# MAX31856_BREAKOUT_x4.net
KiCad netlist of a schematic drawn in EAGLE
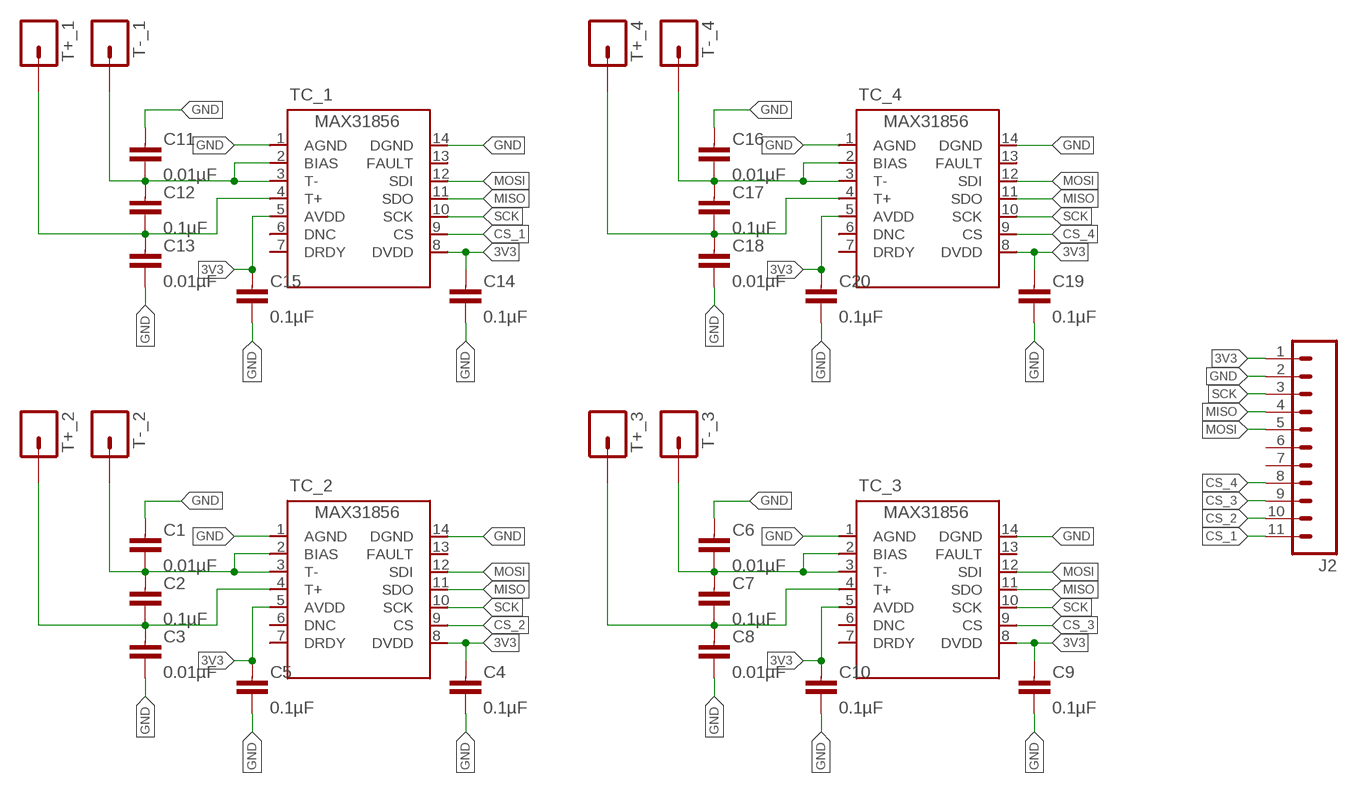
[diagram p0: schematic, sheet 1]

(export (version "E")
  (design (tool "Eeschema 10.0.6"))
  (components
    (comp (ref "C1")
      (value "0.01µF")
      (footprint "eagle-import:C0603-N")
      (libsource (lib "eagle-import") (part "CAPACITOR0603-N"))
    )
    (comp (ref "C2")
      (value "0.1µF")
      (footprint "eagle-import:C0603-N")
      (libsource (lib "eagle-import") (part "CAPACITOR0603-N"))
    )
    (comp (ref "C3")
      (value "0.01µF")
      (footprint "eagle-import:C0603-N")
      (libsource (lib "eagle-import") (part "CAPACITOR0603-N"))
    )
    (comp (ref "C4")
      (value "0.1µF")
      (footprint "eagle-import:C0603-N")
      (libsource (lib "eagle-import") (part "CAPACITOR0603-N"))
    )
    (comp (ref "C5")
      (value "0.1µF")
      (footprint "eagle-import:C0603-N")
      (libsource (lib "eagle-import") (part "CAPACITOR0603-N"))
    )
    (comp (ref "C6")
      (value "0.01µF")
      (footprint "eagle-import:C0603-N")
      (libsource (lib "eagle-import") (part "CAPACITOR0603-N"))
    )
    (comp (ref "C7")
      (value "0.1µF")
      (footprint "eagle-import:C0603-N")
      (libsource (lib "eagle-import") (part "CAPACITOR0603-N"))
    )
    (comp (ref "C8")
      (value "0.01µF")
      (footprint "eagle-import:C0603-N")
      (libsource (lib "eagle-import") (part "CAPACITOR0603-N"))
    )
    (comp (ref "C9")
      (value "0.1µF")
      (footprint "eagle-import:C0603-N")
      (libsource (lib "eagle-import") (part "CAPACITOR0603-N"))
    )
    (comp (ref "C10")
      (value "0.1µF")
      (footprint "eagle-import:C0603-N")
      (libsource (lib "eagle-import") (part "CAPACITOR0603-N"))
    )
    (comp (ref "C11")
      (value "0.01µF")
      (footprint "eagle-import:C0603-N")
      (libsource (lib "eagle-import") (part "CAPACITOR0603-N"))
    )
    (comp (ref "C12")
      (value "0.1µF")
      (footprint "eagle-import:C0603-N")
      (libsource (lib "eagle-import") (part "CAPACITOR0603-N"))
    )
    (comp (ref "C13")
      (value "0.01µF")
      (footprint "eagle-import:C0603-N")
      (libsource (lib "eagle-import") (part "CAPACITOR0603-N"))
    )
    (comp (ref "C14")
      (value "0.1µF")
      (footprint "eagle-import:C0603-N")
      (libsource (lib "eagle-import") (part "CAPACITOR0603-N"))
    )
    (comp (ref "C15")
      (value "0.1µF")
      (footprint "eagle-import:C0603-N")
      (libsource (lib "eagle-import") (part "CAPACITOR0603-N"))
    )
    (comp (ref "C16")
      (value "0.01µF")
      (footprint "eagle-import:C0603-N")
      (libsource (lib "eagle-import") (part "CAPACITOR0603-N"))
    )
    (comp (ref "C17")
      (value "0.1µF")
      (footprint "eagle-import:C0603-N")
      (libsource (lib "eagle-import") (part "CAPACITOR0603-N"))
    )
    (comp (ref "C18")
      (value "0.01µF")
      (footprint "eagle-import:C0603-N")
      (libsource (lib "eagle-import") (part "CAPACITOR0603-N"))
    )
    (comp (ref "C19")
      (value "0.1µF")
      (footprint "eagle-import:C0603-N")
      (libsource (lib "eagle-import") (part "CAPACITOR0603-N"))
    )
    (comp (ref "C20")
      (value "0.1µF")
      (footprint "eagle-import:C0603-N")
      (libsource (lib "eagle-import") (part "CAPACITOR0603-N"))
    )
    (comp (ref "J2")
      (value "M11PTH")
      (footprint "eagle-import:1X11")
      (libsource (lib "eagle-import") (part "M11PTH"))
    )
    (comp (ref "T+_1")
      (value "M01SMD")
      (footprint "eagle-import:LUXEON-PAD")
      (libsource (lib "eagle-import") (part "M01SMD"))
    )
    (comp (ref "T+_2")
      (value "M01SMD")
      (footprint "eagle-import:LUXEON-PAD")
      (libsource (lib "eagle-import") (part "M01SMD"))
    )
    (comp (ref "T+_3")
      (value "M01SMD")
      (footprint "eagle-import:LUXEON-PAD")
      (libsource (lib "eagle-import") (part "M01SMD"))
    )
    (comp (ref "T+_4")
      (value "M01SMD")
      (footprint "eagle-import:LUXEON-PAD")
      (libsource (lib "eagle-import") (part "M01SMD"))
    )
    (comp (ref "T-_1")
      (value "M01SMD")
      (footprint "eagle-import:LUXEON-PAD")
      (libsource (lib "eagle-import") (part "M01SMD"))
    )
    (comp (ref "T-_2")
      (value "M01SMD")
      (footprint "eagle-import:LUXEON-PAD")
      (libsource (lib "eagle-import") (part "M01SMD"))
    )
    (comp (ref "T-_3")
      (value "M01SMD")
      (footprint "eagle-import:LUXEON-PAD")
      (libsource (lib "eagle-import") (part "M01SMD"))
    )
    (comp (ref "T-_4")
      (value "M01SMD")
      (footprint "eagle-import:LUXEON-PAD")
      (libsource (lib "eagle-import") (part "M01SMD"))
    )
    (comp (ref "TC_1")
      (value "MAX31856MUD+")
      (footprint "eagle-import:TSSOP14")
      (libsource (lib "eagle-import") (part "MAX31856MUD+"))
    )
    (comp (ref "TC_2")
      (value "MAX31856MUD+")
      (footprint "eagle-import:TSSOP14")
      (libsource (lib "eagle-import") (part "MAX31856MUD+"))
    )
    (comp (ref "TC_3")
      (value "MAX31856MUD+")
      (footprint "eagle-import:TSSOP14")
      (libsource (lib "eagle-import") (part "MAX31856MUD+"))
    )
    (comp (ref "TC_4")
      (value "MAX31856MUD+")
      (footprint "eagle-import:TSSOP14")
      (libsource (lib "eagle-import") (part "MAX31856MUD+"))
    )
  )
  (nets
    (net (code "1") (name "3V3") (class "Default")
      (node (ref "C10") (pin "1") (pinfunction "1_1") (pintype "passive"))
      (node (ref "C14") (pin "1") (pinfunction "1_1") (pintype "passive"))
      (node (ref "C15") (pin "1") (pinfunction "1_1") (pintype "passive"))
      (node (ref "C19") (pin "1") (pinfunction "1_1") (pintype "passive"))
      (node (ref "C20") (pin "1") (pinfunction "1_1") (pintype "passive"))
      (node (ref "C4") (pin "1") (pinfunction "1_1") (pintype "passive"))
      (node (ref "C5") (pin "1") (pinfunction "1_1") (pintype "passive"))
      (node (ref "C9") (pin "1") (pinfunction "1_1") (pintype "passive"))
      (node (ref "J2") (pin "1") (pinfunction "1_1") (pintype "passive"))
      (node (ref "TC_1") (pin "5") (pinfunction "AVDD_5") (pintype "bidirectional"))
      (node (ref "TC_1") (pin "8") (pinfunction "DVDD_8") (pintype "bidirectional"))
      (node (ref "TC_2") (pin "5") (pinfunction "AVDD_5") (pintype "bidirectional"))
      (node (ref "TC_2") (pin "8") (pinfunction "DVDD_8") (pintype "bidirectional"))
      (node (ref "TC_3") (pin "5") (pinfunction "AVDD_5") (pintype "bidirectional"))
      (node (ref "TC_3") (pin "8") (pinfunction "DVDD_8") (pintype "bidirectional"))
      (node (ref "TC_4") (pin "5") (pinfunction "AVDD_5") (pintype "bidirectional"))
      (node (ref "TC_4") (pin "8") (pinfunction "DVDD_8") (pintype "bidirectional"))
    )
    (net (code "2") (name "CS_1") (class "Default")
      (node (ref "J2") (pin "11") (pinfunction "11_11") (pintype "passive"))
      (node (ref "TC_1") (pin "9") (pinfunction "CS_9") (pintype "bidirectional"))
    )
    (net (code "3") (name "CS_2") (class "Default")
      (node (ref "J2") (pin "10") (pinfunction "10_10") (pintype "passive"))
      (node (ref "TC_2") (pin "9") (pinfunction "CS_9") (pintype "bidirectional"))
    )
    (net (code "4") (name "CS_3") (class "Default")
      (node (ref "J2") (pin "9") (pinfunction "9_9") (pintype "passive"))
      (node (ref "TC_3") (pin "9") (pinfunction "CS_9") (pintype "bidirectional"))
    )
    (net (code "5") (name "CS_4") (class "Default")
      (node (ref "J2") (pin "8") (pinfunction "8_8") (pintype "passive"))
      (node (ref "TC_4") (pin "9") (pinfunction "CS_9") (pintype "bidirectional"))
    )
    (net (code "6") (name "GND") (class "Default")
      (node (ref "C1") (pin "1") (pinfunction "1_1") (pintype "passive"))
      (node (ref "C10") (pin "2") (pinfunction "2_2") (pintype "passive"))
      (node (ref "C11") (pin "1") (pinfunction "1_1") (pintype "passive"))
      (node (ref "C13") (pin "2") (pinfunction "2_2") (pintype "passive"))
      (node (ref "C14") (pin "2") (pinfunction "2_2") (pintype "passive"))
      (node (ref "C15") (pin "2") (pinfunction "2_2") (pintype "passive"))
      (node (ref "C16") (pin "1") (pinfunction "1_1") (pintype "passive"))
      (node (ref "C18") (pin "2") (pinfunction "2_2") (pintype "passive"))
      (node (ref "C19") (pin "2") (pinfunction "2_2") (pintype "passive"))
      (node (ref "C20") (pin "2") (pinfunction "2_2") (pintype "passive"))
      (node (ref "C3") (pin "2") (pinfunction "2_2") (pintype "passive"))
      (node (ref "C4") (pin "2") (pinfunction "2_2") (pintype "passive"))
      (node (ref "C5") (pin "2") (pinfunction "2_2") (pintype "passive"))
      (node (ref "C6") (pin "1") (pinfunction "1_1") (pintype "passive"))
      (node (ref "C8") (pin "2") (pinfunction "2_2") (pintype "passive"))
      (node (ref "C9") (pin "2") (pinfunction "2_2") (pintype "passive"))
      (node (ref "J2") (pin "2") (pinfunction "2_2") (pintype "passive"))
      (node (ref "TC_1") (pin "1") (pinfunction "AGND_1") (pintype "bidirectional"))
      (node (ref "TC_1") (pin "14") (pinfunction "DGND_14") (pintype "bidirectional"))
      (node (ref "TC_2") (pin "1") (pinfunction "AGND_1") (pintype "bidirectional"))
      (node (ref "TC_2") (pin "14") (pinfunction "DGND_14") (pintype "bidirectional"))
      (node (ref "TC_3") (pin "1") (pinfunction "AGND_1") (pintype "bidirectional"))
      (node (ref "TC_3") (pin "14") (pinfunction "DGND_14") (pintype "bidirectional"))
      (node (ref "TC_4") (pin "1") (pinfunction "AGND_1") (pintype "bidirectional"))
      (node (ref "TC_4") (pin "14") (pinfunction "DGND_14") (pintype "bidirectional"))
    )
    (net (code "7") (name "MISO") (class "Default")
      (node (ref "J2") (pin "4") (pinfunction "4_4") (pintype "passive"))
      (node (ref "TC_1") (pin "11") (pinfunction "SDO_11") (pintype "bidirectional"))
      (node (ref "TC_2") (pin "11") (pinfunction "SDO_11") (pintype "bidirectional"))
      (node (ref "TC_3") (pin "11") (pinfunction "SDO_11") (pintype "bidirectional"))
      (node (ref "TC_4") (pin "11") (pinfunction "SDO_11") (pintype "bidirectional"))
    )
    (net (code "8") (name "MOSI") (class "Default")
      (node (ref "J2") (pin "5") (pinfunction "5_5") (pintype "passive"))
      (node (ref "TC_1") (pin "12") (pinfunction "SDI_12") (pintype "bidirectional"))
      (node (ref "TC_2") (pin "12") (pinfunction "SDI_12") (pintype "bidirectional"))
      (node (ref "TC_3") (pin "12") (pinfunction "SDI_12") (pintype "bidirectional"))
      (node (ref "TC_4") (pin "12") (pinfunction "SDI_12") (pintype "bidirectional"))
    )
    (net (code "9") (name "Net-(T+_1-1)") (class "Default")
      (node (ref "C12") (pin "2") (pinfunction "2_2") (pintype "passive"))
      (node (ref "C13") (pin "1") (pinfunction "1_1") (pintype "passive"))
      (node (ref "T+_1") (pin "P$1") (pinfunction "1_P$1") (pintype "passive"))
      (node (ref "TC_1") (pin "4") (pinfunction "T+_4") (pintype "bidirectional"))
    )
    (net (code "10") (name "Net-(T+_2-1)") (class "Default")
      (node (ref "C2") (pin "2") (pinfunction "2_2") (pintype "passive"))
      (node (ref "C3") (pin "1") (pinfunction "1_1") (pintype "passive"))
      (node (ref "T+_2") (pin "P$1") (pinfunction "1_P$1") (pintype "passive"))
      (node (ref "TC_2") (pin "4") (pinfunction "T+_4") (pintype "bidirectional"))
    )
    (net (code "11") (name "Net-(T+_3-1)") (class "Default")
      (node (ref "C7") (pin "2") (pinfunction "2_2") (pintype "passive"))
      (node (ref "C8") (pin "1") (pinfunction "1_1") (pintype "passive"))
      (node (ref "T+_3") (pin "P$1") (pinfunction "1_P$1") (pintype "passive"))
      (node (ref "TC_3") (pin "4") (pinfunction "T+_4") (pintype "bidirectional"))
    )
    (net (code "12") (name "Net-(T+_4-1)") (class "Default")
      (node (ref "C17") (pin "2") (pinfunction "2_2") (pintype "passive"))
      (node (ref "C18") (pin "1") (pinfunction "1_1") (pintype "passive"))
      (node (ref "T+_4") (pin "P$1") (pinfunction "1_P$1") (pintype "passive"))
      (node (ref "TC_4") (pin "4") (pinfunction "T+_4") (pintype "bidirectional"))
    )
    (net (code "13") (name "Net-(T-_1-1)") (class "Default")
      (node (ref "C11") (pin "2") (pinfunction "2_2") (pintype "passive"))
      (node (ref "C12") (pin "1") (pinfunction "1_1") (pintype "passive"))
      (node (ref "T-_1") (pin "P$1") (pinfunction "1_P$1") (pintype "passive"))
      (node (ref "TC_1") (pin "2") (pinfunction "BIAS_2") (pintype "bidirectional"))
      (node (ref "TC_1") (pin "3") (pinfunction "T-_3") (pintype "bidirectional"))
    )
    (net (code "14") (name "Net-(T-_2-1)") (class "Default")
      (node (ref "C1") (pin "2") (pinfunction "2_2") (pintype "passive"))
      (node (ref "C2") (pin "1") (pinfunction "1_1") (pintype "passive"))
      (node (ref "T-_2") (pin "P$1") (pinfunction "1_P$1") (pintype "passive"))
      (node (ref "TC_2") (pin "2") (pinfunction "BIAS_2") (pintype "bidirectional"))
      (node (ref "TC_2") (pin "3") (pinfunction "T-_3") (pintype "bidirectional"))
    )
    (net (code "15") (name "Net-(T-_3-1)") (class "Default")
      (node (ref "C6") (pin "2") (pinfunction "2_2") (pintype "passive"))
      (node (ref "C7") (pin "1") (pinfunction "1_1") (pintype "passive"))
      (node (ref "T-_3") (pin "P$1") (pinfunction "1_P$1") (pintype "passive"))
      (node (ref "TC_3") (pin "2") (pinfunction "BIAS_2") (pintype "bidirectional"))
      (node (ref "TC_3") (pin "3") (pinfunction "T-_3") (pintype "bidirectional"))
    )
    (net (code "16") (name "Net-(T-_4-1)") (class "Default")
      (node (ref "C16") (pin "2") (pinfunction "2_2") (pintype "passive"))
      (node (ref "C17") (pin "1") (pinfunction "1_1") (pintype "passive"))
      (node (ref "T-_4") (pin "P$1") (pinfunction "1_P$1") (pintype "passive"))
      (node (ref "TC_4") (pin "2") (pinfunction "BIAS_2") (pintype "bidirectional"))
      (node (ref "TC_4") (pin "3") (pinfunction "T-_3") (pintype "bidirectional"))
    )
    (net (code "17") (name "SCK") (class "Default")
      (node (ref "J2") (pin "3") (pinfunction "3_3") (pintype "passive"))
      (node (ref "TC_1") (pin "10") (pinfunction "SCK_10") (pintype "bidirectional"))
      (node (ref "TC_2") (pin "10") (pinfunction "SCK_10") (pintype "bidirectional"))
      (node (ref "TC_3") (pin "10") (pinfunction "SCK_10") (pintype "bidirectional"))
      (node (ref "TC_4") (pin "10") (pinfunction "SCK_10") (pintype "bidirectional"))
    )
    (net (code "18") (name "unconnected-(J2-Pad6)") (class "Default")
      (node (ref "J2") (pin "6") (pinfunction "6_6") (pintype "passive"))
    )
    (net (code "19") (name "unconnected-(J2-Pad7)") (class "Default")
      (node (ref "J2") (pin "7") (pinfunction "7_7") (pintype "passive"))
    )
    (net (code "20") (name "unconnected-(TC_1-DNC-Pad6)") (class "Default")
      (node (ref "TC_1") (pin "6") (pinfunction "DNC_6") (pintype "bidirectional"))
    )
    (net (code "21") (name "unconnected-(TC_1-DRDY-Pad7)") (class "Default")
      (node (ref "TC_1") (pin "7") (pinfunction "DRDY_7") (pintype "bidirectional"))
    )
    (net (code "22") (name "unconnected-(TC_1-FAULT-Pad13)") (class "Default")
      (node (ref "TC_1") (pin "13") (pinfunction "FAULT_13") (pintype "bidirectional"))
    )
    (net (code "23") (name "unconnected-(TC_2-DNC-Pad6)") (class "Default")
      (node (ref "TC_2") (pin "6") (pinfunction "DNC_6") (pintype "bidirectional"))
    )
    (net (code "24") (name "unconnected-(TC_2-DRDY-Pad7)") (class "Default")
      (node (ref "TC_2") (pin "7") (pinfunction "DRDY_7") (pintype "bidirectional"))
    )
    (net (code "25") (name "unconnected-(TC_2-FAULT-Pad13)") (class "Default")
      (node (ref "TC_2") (pin "13") (pinfunction "FAULT_13") (pintype "bidirectional"))
    )
    (net (code "26") (name "unconnected-(TC_3-DNC-Pad6)") (class "Default")
      (node (ref "TC_3") (pin "6") (pinfunction "DNC_6") (pintype "bidirectional"))
    )
    (net (code "27") (name "unconnected-(TC_3-DRDY-Pad7)") (class "Default")
      (node (ref "TC_3") (pin "7") (pinfunction "DRDY_7") (pintype "bidirectional"))
    )
    (net (code "28") (name "unconnected-(TC_3-FAULT-Pad13)") (class "Default")
      (node (ref "TC_3") (pin "13") (pinfunction "FAULT_13") (pintype "bidirectional"))
    )
    (net (code "29") (name "unconnected-(TC_4-DNC-Pad6)") (class "Default")
      (node (ref "TC_4") (pin "6") (pinfunction "DNC_6") (pintype "bidirectional"))
    )
    (net (code "30") (name "unconnected-(TC_4-DRDY-Pad7)") (class "Default")
      (node (ref "TC_4") (pin "7") (pinfunction "DRDY_7") (pintype "bidirectional"))
    )
    (net (code "31") (name "unconnected-(TC_4-FAULT-Pad13)") (class "Default")
      (node (ref "TC_4") (pin "13") (pinfunction "FAULT_13") (pintype "bidirectional"))
    )
  )
)
